# isolation.net
KiCad netlist of a schematic drawn in Altium Designer
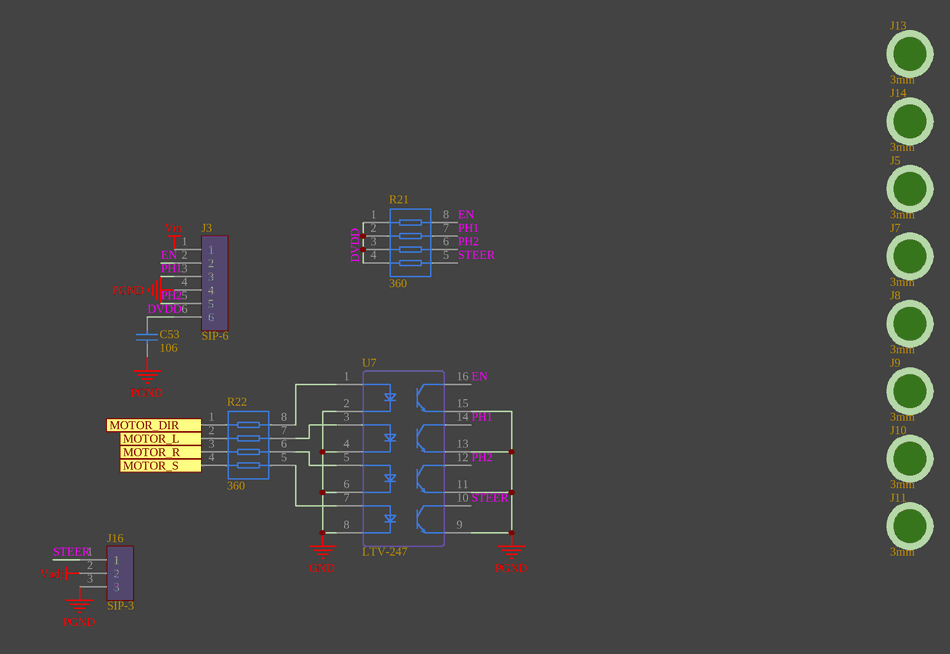
[diagram p0: isolation.SchDoc]

(export (version "E")
  (design (tool "Eeschema 10.0.6"))
  (components
    (comp (ref "C53")
      (value "106")
      (footprint "C0603")
      (description "Capacitor")
      (fields (field (name "PUBLISHER") "Altium Limited"))
      (libsource (lib "iMag") (part "电容"))
    )
    (comp (ref "J3") (value "SIP-6") (footprint "PH2.0-6_SMD") (libsource (lib "iMag") (part "SIP-6")))
    (comp (ref "J5") (value "3mm") (footprint "定位孔 3mm") (libsource (lib "iMag") (part "定位孔")))
    (comp (ref "J7") (value "3mm") (footprint "定位孔 3mm") (libsource (lib "iMag") (part "定位孔")))
    (comp (ref "J8") (value "3mm") (footprint "定位孔 3mm") (libsource (lib "iMag") (part "定位孔")))
    (comp (ref "J9") (value "3mm") (footprint "定位孔 3mm") (libsource (lib "iMag") (part "定位孔")))
    (comp (ref "J10") (value "3mm") (footprint "定位孔 3mm") (libsource (lib "iMag") (part "定位孔")))
    (comp (ref "J11") (value "3mm") (footprint "定位孔 3mm") (libsource (lib "iMag") (part "定位孔")))
    (comp (ref "J13") (value "3mm") (footprint "定位孔 3mm") (libsource (lib "iMag") (part "定位孔")))
    (comp (ref "J14") (value "3mm") (footprint "定位孔 3mm") (libsource (lib "iMag") (part "定位孔")))
    (comp (ref "J16") (value "SIP-3") (footprint "2.54排针1X3") (libsource (lib "iMag") (part "SIP-3")))
    (comp (ref "R21")
      (value "360")
      (footprint "0603_Rx4")
      (description "贴片排阻")
      (libsource (lib "iMag") (part "贴片排阻*4"))
    )
    (comp (ref "R22")
      (value "360")
      (footprint "0603_Rx4")
      (description "贴片排阻")
      (libsource (lib "iMag") (part "贴片排阻*4"))
    )
    (comp (ref "U7")
      (value "LTV-247")
      (footprint "WSOP-16")
      (fields (field (name "BOM_SUPPLIER PART") "C115451") (field (name "CONTRIBUTOR") "LCSC"))
      (libsource (lib "iMag") (part "4光耦"))
    )
  )
  (nets
    (net (code "1") (name "/DVDD") (class "Default")
      (node (ref "C53") (pin "2") (pinfunction "2_2") (pintype "passive"))
      (node (ref "J3") (pin "6") (pinfunction "6_6") (pintype "passive"))
      (node (ref "R21") (pin "1") (pinfunction "1_1") (pintype "passive"))
      (node (ref "R21") (pin "2") (pinfunction "2_2") (pintype "passive"))
      (node (ref "R21") (pin "3") (pinfunction "3_3") (pintype "passive"))
      (node (ref "R21") (pin "4") (pinfunction "4_4") (pintype "passive"))
    )
    (net (code "2") (name "/EN") (class "Default")
      (node (ref "J3") (pin "2") (pinfunction "2_2") (pintype "passive"))
      (node (ref "R21") (pin "8") (pinfunction "8_8") (pintype "passive"))
      (node (ref "U7") (pin "16") (pinfunction "COL1_16") (pintype "passive"))
    )
    (net (code "3") (name "/MOTOR_DIR") (class "Default")
      (node (ref "R22") (pin "1") (pinfunction "1_1") (pintype "passive"))
    )
    (net (code "4") (name "/MOTOR_L") (class "Default")
      (node (ref "R22") (pin "2") (pinfunction "2_2") (pintype "passive"))
    )
    (net (code "5") (name "/MOTOR_R") (class "Default")
      (node (ref "R22") (pin "3") (pinfunction "3_3") (pintype "passive"))
    )
    (net (code "6") (name "/MOTOR_S") (class "Default")
      (node (ref "R22") (pin "4") (pinfunction "4_4") (pintype "passive"))
    )
    (net (code "7") (name "/PH1") (class "Default")
      (node (ref "J3") (pin "3") (pinfunction "3_3") (pintype "passive"))
      (node (ref "R21") (pin "7") (pinfunction "7_7") (pintype "passive"))
      (node (ref "U7") (pin "14") (pinfunction "COL2_14") (pintype "passive"))
    )
    (net (code "8") (name "/PH2") (class "Default")
      (node (ref "J3") (pin "5") (pinfunction "5_5") (pintype "passive"))
      (node (ref "R21") (pin "6") (pinfunction "6_6") (pintype "passive"))
      (node (ref "U7") (pin "12") (pinfunction "COL3_12") (pintype "passive"))
    )
    (net (code "9") (name "/STEER") (class "Default")
      (node (ref "J16") (pin "1") (pinfunction "1_1") (pintype "passive"))
      (node (ref "R21") (pin "5") (pinfunction "5_5") (pintype "passive"))
      (node (ref "U7") (pin "10") (pinfunction "COL4_10") (pintype "passive"))
    )
    (net (code "10") (name "GND") (class "Default")
      (node (ref "U7") (pin "2") (pinfunction "CAT1_2") (pintype "passive"))
      (node (ref "U7") (pin "4") (pinfunction "CAT2_4") (pintype "passive"))
      (node (ref "U7") (pin "6") (pinfunction "CAT3_6") (pintype "passive"))
      (node (ref "U7") (pin "8") (pinfunction "CAT4_8") (pintype "passive"))
    )
    (net (code "11") (name "Net-(U7-AN1)") (class "Default")
      (node (ref "R22") (pin "8") (pinfunction "8_8") (pintype "passive"))
      (node (ref "U7") (pin "1") (pinfunction "AN1_1") (pintype "passive"))
    )
    (net (code "12") (name "Net-(U7-AN2)") (class "Default")
      (node (ref "R22") (pin "7") (pinfunction "7_7") (pintype "passive"))
      (node (ref "U7") (pin "3") (pinfunction "AN2_3") (pintype "passive"))
    )
    (net (code "13") (name "Net-(U7-AN3)") (class "Default")
      (node (ref "R22") (pin "6") (pinfunction "6_6") (pintype "passive"))
      (node (ref "U7") (pin "5") (pinfunction "AN3_5") (pintype "passive"))
    )
    (net (code "14") (name "Net-(U7-AN4)") (class "Default")
      (node (ref "R22") (pin "5") (pinfunction "5_5") (pintype "passive"))
      (node (ref "U7") (pin "7") (pinfunction "AN4_7") (pintype "passive"))
    )
    (net (code "15") (name "PGND") (class "Default")
      (node (ref "C53") (pin "1") (pinfunction "1_1") (pintype "passive"))
      (node (ref "J16") (pin "3") (pinfunction "3_3") (pintype "passive"))
      (node (ref "J3") (pin "4") (pinfunction "4_4") (pintype "passive"))
      (node (ref "U7") (pin "11") (pinfunction "EM3_11") (pintype "passive"))
      (node (ref "U7") (pin "13") (pinfunction "EM2_13") (pintype "passive"))
      (node (ref "U7") (pin "15") (pinfunction "EM1_15") (pintype "passive"))
      (node (ref "U7") (pin "9") (pinfunction "EM4_9") (pintype "passive"))
    )
    (net (code "16") (name "Vadj") (class "Default")
      (node (ref "J16") (pin "2") (pinfunction "2_2") (pintype "passive"))
    )
    (net (code "17") (name "Vm") (class "Default")
      (node (ref "J3") (pin "1") (pinfunction "1_1") (pintype "passive"))
    )
  )
)
